# 1500-GPS.net
KiCad netlist of a schematic drawn in Altium Designer
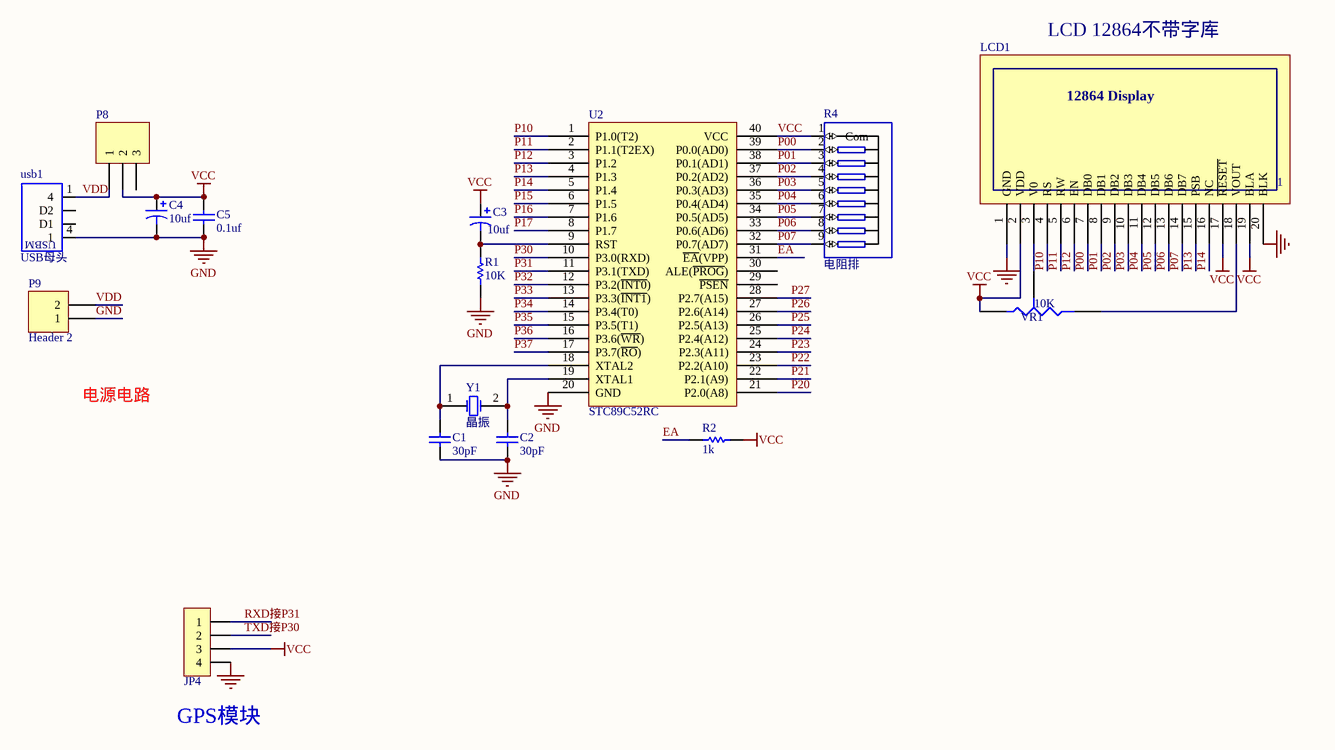
[diagram p0: 单号1500-GPS解析.SchDoc]

(export (version "E")
  (design (tool "Eeschema 10.0.6"))
  (components
    (comp (ref "C1")
      (value "30pF")
      (footprint "RAD-0.1")
      (description "Capacitor")
      (fields (field (name "Comment") "瓷片电容") (field (name "PUBLISHER") "Altium Limited"))
      (libsource (lib "Miscellaneous Devices") (part "Cap"))
    )
    (comp (ref "C2")
      (value "30pF")
      (footprint "RAD-0.1")
      (description "Capacitor")
      (fields (field (name "Comment") "瓷片电容") (field (name "PUBLISHER") "Altium Limited"))
      (libsource (lib "Miscellaneous Devices") (part "Cap"))
    )
    (comp (ref "C3")
      (value "10uf")
      (footprint "10UF")
      (description "Polarized Capacitor (Radial)")
      (fields (field (name "Comment") "电解电容") (field (name "PUBLISHER") "Altium Limited"))
      (libsource (lib "Miscellaneous Devices") (part "Cap Pol1"))
    )
    (comp (ref "C4")
      (value "10uf")
      (footprint "10UF")
      (description "Polarized Capacitor (Radial)")
      (fields (field (name "Comment") "点解电容") (field (name "PUBLISHER") "Altium Limited"))
      (libsource (lib "Miscellaneous Devices") (part "Cap Pol1"))
    )
    (comp (ref "C5")
      (value "0.1uf")
      (footprint "CB1")
      (description "Capacitor")
      (fields (field (name "Comment") "瓷片电容") (field (name "PUBLISHER") "Altium Limited"))
      (libsource (lib "Miscellaneous Devices") (part "Cap"))
    )
    (comp (ref "JP4")
      (value "HDR-1X4")
      (footprint "HDR-1X4")
      (description "4P接插件")
      (libsource (lib "接插件") (part "Header 4"))
    )
    (comp (ref "LCD1") (value "1") (footprint "12864") (libsource (lib "*") (part "LCD12864-CK")))
    (comp (ref "P8")
      (value "Header 3")
      (footprint "HDR1X3")
      (description "Header, 3-Pin")
      (fields (field (name "PUBLISHER") "Altium Limited"))
      (libsource (lib "Miscellaneous Connectors") (part "Header 3"))
    )
    (comp (ref "P9")
      (value "Header 2")
      (footprint "HDR1X2")
      (description "Header, 2-Pin")
      (fields (field (name "PUBLISHER") "Altium Limited"))
      (libsource (lib "Miscellaneous Connectors") (part "Header 2"))
    )
    (comp (ref "R1")
      (value "10K")
      (footprint "电阻0.7-1.6")
      (description "Resistor")
      (fields (field (name "Comment") "电阻") (field (name "PUBLISHER") "Altium Limited"))
      (libsource (lib "Miscellaneous Devices") (part "Res1"))
    )
    (comp (ref "R2")
      (value "1k")
      (footprint "电阻0.7-1.6")
      (description "Resistor")
      (fields (field (name "Comment") "电阻") (field (name "PUBLISHER") "Altium Limited"))
      (libsource (lib "Miscellaneous Devices") (part "Res1"))
    )
    (comp (ref "R4") (value "电阻排") (footprint "插槽P9") (libsource (lib "电阻") (part "RES10")))
    (comp (ref "U2") (value "STC89C52RC") (footprint "DIP-40W") (libsource (lib "51单片机") (part "89C52")))
    (comp (ref "usb1") (value "USB母头") (footprint "A母USB") (libsource (lib "常用2") (part "USB")))
    (comp (ref "VR1")
      (value "12864")
      (footprint "RW")
      (fields (field (name "ALTIUM_UNNAMED_1") "10K"))
      (libsource (lib "*") (part "RES-TAP"))
    )
    (comp (ref "Y1")
      (value "晶振")
      (footprint "XTAL")
      (description "Crystal Oscillator")
      (fields (field (name "PUBLISHER") "Altium Limited"))
      (libsource (lib "Miscellaneous Devices") (part "XTAL"))
    )
  )
  (nets
    (net (code "1") (name "/EA") (class "Default")
      (node (ref "R2") (pin "2") (pinfunction "2_2") (pintype "passive"))
      (node (ref "U2") (pin "31") (pinfunction "~{EA}(VPP)_31") (pintype "passive"))
    )
    (net (code "3") (name "/P00") (class "Default")
      (node (ref "LCD1") (pin "7") (pinfunction "DB0_7") (pintype "passive"))
      (node (ref "R4") (pin "2") (pinfunction "2_2") (pintype "bidirectional"))
      (node (ref "U2") (pin "39") (pinfunction "P0.0(AD0)_39") (pintype "passive"))
    )
    (net (code "4") (name "/P01") (class "Default")
      (node (ref "LCD1") (pin "8") (pinfunction "DB1_8") (pintype "passive"))
      (node (ref "R4") (pin "3") (pinfunction "3_3") (pintype "bidirectional"))
      (node (ref "U2") (pin "38") (pinfunction "P0.1(AD1)_38") (pintype "passive"))
    )
    (net (code "5") (name "/P02") (class "Default")
      (node (ref "LCD1") (pin "9") (pinfunction "DB2_9") (pintype "passive"))
      (node (ref "R4") (pin "4") (pinfunction "4_4") (pintype "bidirectional"))
      (node (ref "U2") (pin "37") (pinfunction "P0.2(AD2)_37") (pintype "passive"))
    )
    (net (code "6") (name "/P03") (class "Default")
      (node (ref "LCD1") (pin "10") (pinfunction "DB3_10") (pintype "passive"))
      (node (ref "R4") (pin "5") (pinfunction "5_5") (pintype "bidirectional"))
      (node (ref "U2") (pin "36") (pinfunction "P0.3(AD3)_36") (pintype "passive"))
    )
    (net (code "7") (name "/P04") (class "Default")
      (node (ref "LCD1") (pin "11") (pinfunction "DB4_11") (pintype "passive"))
      (node (ref "R4") (pin "6") (pinfunction "6_6") (pintype "bidirectional"))
      (node (ref "U2") (pin "35") (pinfunction "P0.4(AD4)_35") (pintype "passive"))
    )
    (net (code "8") (name "/P05") (class "Default")
      (node (ref "LCD1") (pin "12") (pinfunction "DB5_12") (pintype "passive"))
      (node (ref "R4") (pin "7") (pinfunction "7_7") (pintype "bidirectional"))
      (node (ref "U2") (pin "34") (pinfunction "P0.5(AD5)_34") (pintype "passive"))
    )
    (net (code "9") (name "/P06") (class "Default")
      (node (ref "LCD1") (pin "13") (pinfunction "DB6_13") (pintype "passive"))
      (node (ref "R4") (pin "8") (pinfunction "8_8") (pintype "bidirectional"))
      (node (ref "U2") (pin "33") (pinfunction "P0.6(AD6)_33") (pintype "passive"))
    )
    (net (code "10") (name "/P07") (class "Default")
      (node (ref "LCD1") (pin "14") (pinfunction "DB7_14") (pintype "passive"))
      (node (ref "R4") (pin "9") (pinfunction "9_9") (pintype "bidirectional"))
      (node (ref "U2") (pin "32") (pinfunction "P0.7(AD7)_32") (pintype "passive"))
    )
    (net (code "11") (name "/P10") (class "Default")
      (node (ref "LCD1") (pin "4") (pinfunction "RS_4") (pintype "passive"))
      (node (ref "U2") (pin "1") (pinfunction "P1.0(T2)_1") (pintype "passive"))
    )
    (net (code "12") (name "/P11") (class "Default")
      (node (ref "LCD1") (pin "5") (pinfunction "RW_5") (pintype "passive"))
      (node (ref "U2") (pin "2") (pinfunction "P1.1(T2EX)_2") (pintype "passive"))
    )
    (net (code "13") (name "/P12") (class "Default")
      (node (ref "LCD1") (pin "6") (pinfunction "EN_6") (pintype "passive"))
      (node (ref "U2") (pin "3") (pinfunction "P1.2_3") (pintype "passive"))
    )
    (net (code "14") (name "/P13") (class "Default")
      (node (ref "LCD1") (pin "15") (pinfunction "PSB_15") (pintype "passive"))
      (node (ref "U2") (pin "4") (pinfunction "P1.3_4") (pintype "passive"))
    )
    (net (code "15") (name "/P14") (class "Default")
      (node (ref "LCD1") (pin "16") (pinfunction "NC_16") (pintype "passive"))
      (node (ref "U2") (pin "5") (pinfunction "P1.4_5") (pintype "passive"))
    )
    (net (code "16") (name "/P15") (class "Default")
      (node (ref "U2") (pin "6") (pinfunction "P1.5_6") (pintype "passive"))
    )
    (net (code "17") (name "/P16") (class "Default")
      (node (ref "U2") (pin "7") (pinfunction "P1.6_7") (pintype "passive"))
    )
    (net (code "18") (name "/P17") (class "Default")
      (node (ref "U2") (pin "8") (pinfunction "P1.7_8") (pintype "passive"))
    )
    (net (code "19") (name "/P20") (class "Default")
      (node (ref "U2") (pin "21") (pinfunction "P2.0(A8)_21") (pintype "passive"))
    )
    (net (code "20") (name "/P21") (class "Default")
      (node (ref "U2") (pin "22") (pinfunction "P2.1(A9)_22") (pintype "passive"))
    )
    (net (code "21") (name "/P22") (class "Default")
      (node (ref "U2") (pin "23") (pinfunction "P2.2(A10)_23") (pintype "passive"))
    )
    (net (code "22") (name "/P23") (class "Default")
      (node (ref "U2") (pin "24") (pinfunction "P2.3(A11)_24") (pintype "passive"))
    )
    (net (code "23") (name "/P24") (class "Default")
      (node (ref "U2") (pin "25") (pinfunction "P2.4(A12)_25") (pintype "passive"))
    )
    (net (code "24") (name "/P25") (class "Default")
      (node (ref "U2") (pin "26") (pinfunction "P2.5(A13)_26") (pintype "passive"))
    )
    (net (code "25") (name "/P26") (class "Default")
      (node (ref "U2") (pin "27") (pinfunction "P2.6(A14)_27") (pintype "passive"))
    )
    (net (code "26") (name "/P27") (class "Default")
      (node (ref "U2") (pin "28") (pinfunction "P2.7(A15)_28") (pintype "passive"))
    )
    (net (code "27") (name "/P30") (class "Default")
      (node (ref "U2") (pin "10") (pinfunction "P3.0(RXD)_10") (pintype "passive"))
    )
    (net (code "28") (name "/P31") (class "Default")
      (node (ref "U2") (pin "11") (pinfunction "P3.1(TXD)_11") (pintype "passive"))
    )
    (net (code "29") (name "/P32") (class "Default")
      (node (ref "U2") (pin "12") (pinfunction "P3.2(~{INT0})_12") (pintype "passive"))
    )
    (net (code "30") (name "/P33") (class "Default")
      (node (ref "U2") (pin "13") (pinfunction "P3.3(~{INT1})_13") (pintype "passive"))
    )
    (net (code "31") (name "/P34") (class "Default")
      (node (ref "U2") (pin "14") (pinfunction "P3.4(T0)_14") (pintype "passive"))
    )
    (net (code "32") (name "/P35") (class "Default")
      (node (ref "U2") (pin "15") (pinfunction "P3.5(T1)_15") (pintype "passive"))
    )
    (net (code "33") (name "/P36") (class "Default")
      (node (ref "U2") (pin "16") (pinfunction "P3.6(~{WR})_16") (pintype "passive"))
    )
    (net (code "34") (name "/P37") (class "Default")
      (node (ref "U2") (pin "17") (pinfunction "P3.7(~{RO})_17") (pintype "passive"))
    )
    (net (code "35") (name "/RXD接P31") (class "Default")
      (node (ref "JP4") (pin "1") (pinfunction "1_1") (pintype "passive"))
    )
    (net (code "36") (name "/TXD接P30") (class "Default")
      (node (ref "JP4") (pin "2") (pinfunction "2_2") (pintype "passive"))
    )
    (net (code "37") (name "/VDD") (class "Default")
      (node (ref "P8") (pin "1") (pinfunction "1_1") (pintype "passive"))
      (node (ref "P9") (pin "2") (pinfunction "2_2") (pintype "passive"))
      (node (ref "usb1") (pin "1") (pinfunction "4_1") (pintype "passive"))
    )
    (net (code "38") (name "GND") (class "Default")
      (node (ref "C1") (pin "1") (pinfunction "1_1") (pintype "passive"))
      (node (ref "C2") (pin "1") (pinfunction "1_1") (pintype "passive"))
      (node (ref "C4") (pin "2") (pinfunction "2_2") (pintype "passive"))
      (node (ref "C5") (pin "1") (pinfunction "1_1") (pintype "passive"))
      (node (ref "JP4") (pin "4") (pinfunction "4_4") (pintype "passive"))
      (node (ref "LCD1") (pin "1") (pinfunction "GND_1") (pintype "passive"))
      (node (ref "LCD1") (pin "20") (pinfunction "BLK_20") (pintype "passive"))
      (node (ref "P9") (pin "1") (pinfunction "1_1") (pintype "passive"))
      (node (ref "R1") (pin "1") (pinfunction "1_1") (pintype "passive"))
      (node (ref "U2") (pin "20") (pinfunction "GND_20") (pintype "passive"))
      (node (ref "usb1") (pin "4") (pinfunction "1_4") (pintype "passive"))
    )
    (net (code "39") (name "Net-(LCD1-V0)") (class "Default")
      (node (ref "LCD1") (pin "3") (pinfunction "V0_3") (pintype "passive"))
      (node (ref "VR1") (pin "2") (pinfunction "2_2") (pintype "passive"))
    )
    (net (code "40") (name "Net-(LCD1-VOUT)") (class "Default")
      (node (ref "LCD1") (pin "18") (pinfunction "VOUT_18") (pintype "passive"))
      (node (ref "VR1") (pin "3") (pinfunction "3_3") (pintype "passive"))
    )
    (net (code "41") (name "Net-(U2-RST)") (class "Default")
      (node (ref "C3") (pin "2") (pinfunction "2_2") (pintype "passive"))
      (node (ref "R1") (pin "2") (pinfunction "2_2") (pintype "passive"))
      (node (ref "U2") (pin "9") (pinfunction "RST_9") (pintype "passive"))
    )
    (net (code "42") (name "Net-(U2-XTAL1)") (class "Default")
      (node (ref "C2") (pin "2") (pinfunction "2_2") (pintype "passive"))
      (node (ref "U2") (pin "19") (pinfunction "XTAL1_19") (pintype "passive"))
      (node (ref "Y1") (pin "2") (pinfunction "OSC2_2") (pintype "passive"))
    )
    (net (code "43") (name "Net-(U2-XTAL2)") (class "Default")
      (node (ref "C1") (pin "2") (pinfunction "2_2") (pintype "passive"))
      (node (ref "U2") (pin "18") (pinfunction "XTAL2_18") (pintype "passive"))
      (node (ref "Y1") (pin "1") (pinfunction "OSC1_1") (pintype "passive"))
    )
    (net (code "44") (name "VCC") (class "Default")
      (node (ref "C3") (pin "1") (pinfunction "1_1") (pintype "passive"))
      (node (ref "C4") (pin "1") (pinfunction "1_1") (pintype "passive"))
      (node (ref "C5") (pin "2") (pinfunction "2_2") (pintype "passive"))
      (node (ref "JP4") (pin "3") (pinfunction "3_3") (pintype "passive"))
      (node (ref "LCD1") (pin "17") (pinfunction "~{RESET}_17") (pintype "passive"))
      (node (ref "LCD1") (pin "19") (pinfunction "BLA_19") (pintype "passive"))
      (node (ref "LCD1") (pin "2") (pinfunction "VDD_2") (pintype "passive"))
      (node (ref "P8") (pin "2") (pinfunction "2_2") (pintype "passive"))
      (node (ref "R2") (pin "1") (pinfunction "1_1") (pintype "passive"))
      (node (ref "R4") (pin "1") (pinfunction "Com_1") (pintype "bidirectional"))
      (node (ref "U2") (pin "40") (pinfunction "VCC_40") (pintype "passive"))
      (node (ref "VR1") (pin "1") (pinfunction "1_1") (pintype "passive"))
    )
    (net (code "45") (name "unconnected-(P8-Pad3)") (class "Default")
      (node (ref "P8") (pin "3") (pinfunction "3_3") (pintype "passive"))
    )
    (net (code "46") (name "unconnected-(U2-ALE(~{PROG})-Pad30)") (class "Default")
      (node (ref "U2") (pin "30") (pinfunction "ALE(~{PROG})_30") (pintype "passive"))
    )
    (net (code "47") (name "unconnected-(U2-~{PSEN}-Pad29)") (class "Default")
      (node (ref "U2") (pin "29") (pinfunction "~{PSEN}_29") (pintype "passive"))
    )
    (net (code "48") (name "unconnected-(usb1-PadD1)") (class "Default")
      (node (ref "usb1") (pin "D1") (pinfunction "D1_D1") (pintype "passive"))
    )
    (net (code "49") (name "unconnected-(usb1-PadD2)") (class "Default")
      (node (ref "usb1") (pin "D2") (pinfunction "D2_D2") (pintype "passive"))
    )
  )
)
